# V_18.net
KiCad netlist of a schematic drawn in Altium Designer
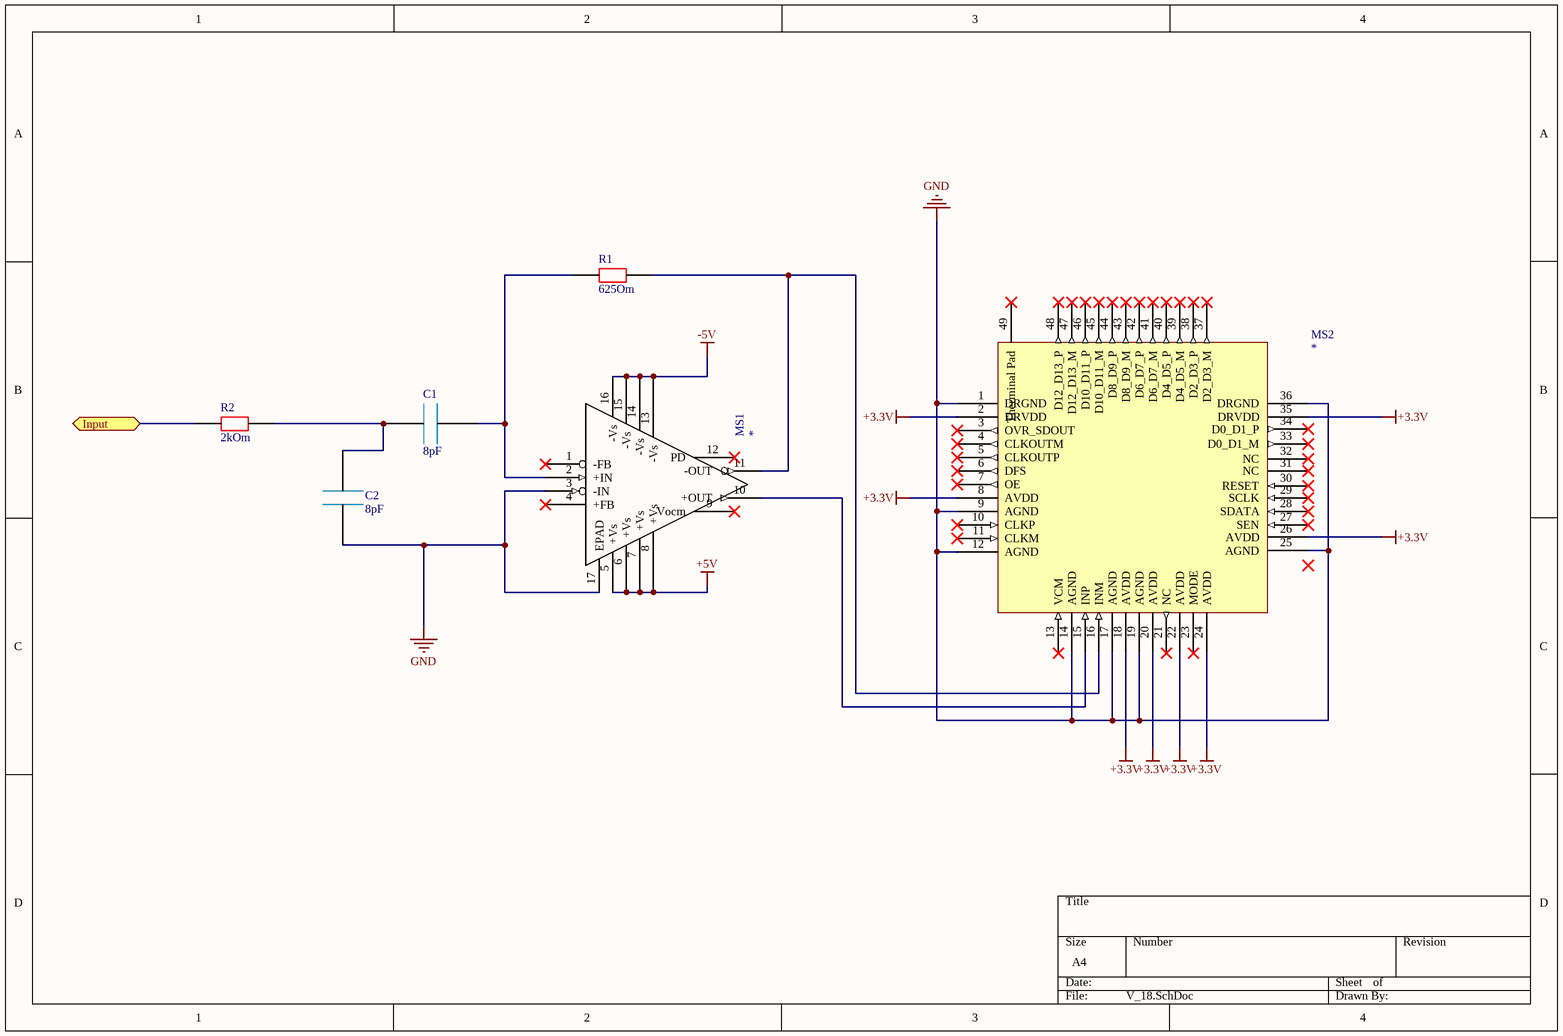
[diagram p0: V_18.SchDoc]

(export (version "E")
  (design (tool "Eeschema 10.0.6"))
  (components
    (comp (ref "C1") (value "8pF") (footprint "V_18:Ñ1") (libsource (lib "V_18") (part "Ñ1")))
    (comp (ref "C2") (value "8pF") (footprint "V_18:Ñ1") (libsource (lib "V_18") (part "Ñ1")))
    (comp (ref "MS1") (value "*") (footprint "V_18:ADA4932") (libsource (lib "V_18") (part "ADA4932")))
    (comp (ref "MS2") (value "*") (footprint "V_18:ADS61B49") (libsource (lib "V_18") (part "ADS61B49")))
    (comp (ref "R1") (value "625Om") (footprint "V_18:Res0805") (libsource (lib "V_18") (part "Res")))
    (comp (ref "R2") (value "2kOm") (footprint "V_18:Res0805") (libsource (lib "V_18") (part "Res")))
  )
  (nets
    (net (code "1") (name "+3.3V") (class "Default")
      (node (ref "MS2") (pin "18") (pinfunction "AVDD_18") (pintype "power_in"))
      (node (ref "MS2") (pin "2") (pinfunction "DRVDD_2") (pintype "power_in"))
      (node (ref "MS2") (pin "20") (pinfunction "AVDD_20") (pintype "power_in"))
      (node (ref "MS2") (pin "22") (pinfunction "AVDD_22") (pintype "power_in"))
      (node (ref "MS2") (pin "24") (pinfunction "AVDD_24") (pintype "power_in"))
      (node (ref "MS2") (pin "26") (pinfunction "AVDD_26") (pintype "power_in"))
      (node (ref "MS2") (pin "35") (pinfunction "DRVDD_35") (pintype "power_in"))
      (node (ref "MS2") (pin "8") (pinfunction "AVDD_8") (pintype "power_in"))
    )
    (net (code "2") (name "+5V") (class "Default")
      (node (ref "MS1") (pin "5") (pinfunction "+Vs_5") (pintype "power_in"))
      (node (ref "MS1") (pin "6") (pinfunction "+Vs_6") (pintype "power_in"))
      (node (ref "MS1") (pin "7") (pinfunction "+Vs_7") (pintype "power_in"))
      (node (ref "MS1") (pin "8") (pinfunction "+Vs_8") (pintype "power_in"))
    )
    (net (code "3") (name "-5V") (class "Default")
      (node (ref "MS1") (pin "13") (pinfunction "-Vs_13") (pintype "power_in"))
      (node (ref "MS1") (pin "14") (pinfunction "-Vs_14") (pintype "power_in"))
      (node (ref "MS1") (pin "15") (pinfunction "-Vs_15") (pintype "power_in"))
      (node (ref "MS1") (pin "16") (pinfunction "-Vs_16") (pintype "power_in"))
    )
    (net (code "4") (name "/Input") (class "Default")
      (node (ref "R2") (pin "1") (pinfunction "1_1") (pintype "passive"))
    )
    (net (code "5") (name "GND") (class "Default")
      (node (ref "C2") (pin "54") (pinfunction "54_54") (pintype "passive"))
      (node (ref "MS1") (pin "17") (pinfunction "EPAD_17") (pintype "power_in"))
      (node (ref "MS1") (pin "3") (pinfunction "-IN_3") (pintype "input"))
      (node (ref "MS2") (pin "1") (pinfunction "DRGND_1") (pintype "power_in"))
      (node (ref "MS2") (pin "12") (pinfunction "AGND_12") (pintype "power_in"))
      (node (ref "MS2") (pin "14") (pinfunction "AGND_14") (pintype "power_in"))
      (node (ref "MS2") (pin "17") (pinfunction "AGND_17") (pintype "power_in"))
      (node (ref "MS2") (pin "19") (pinfunction "AGND_19") (pintype "power_in"))
      (node (ref "MS2") (pin "25") (pinfunction "AGND_25") (pintype "power_in"))
      (node (ref "MS2") (pin "36") (pinfunction "DRGND_36") (pintype "power_in"))
      (node (ref "MS2") (pin "9") (pinfunction "AGND_9") (pintype "power_in"))
    )
    (net (code "6") (name "Net-(C1-Pad53)") (class "Default")
      (node (ref "C1") (pin "53") (pinfunction "53_53") (pintype "passive"))
      (node (ref "C2") (pin "53") (pinfunction "53_53") (pintype "passive"))
      (node (ref "R2") (pin "2") (pinfunction "2_2") (pintype "passive"))
    )
    (net (code "7") (name "Net-(MS1-+IN)") (class "Default")
      (node (ref "C1") (pin "54") (pinfunction "54_54") (pintype "passive"))
      (node (ref "MS1") (pin "2") (pinfunction "+IN_2") (pintype "input"))
      (node (ref "R1") (pin "1") (pinfunction "1_1") (pintype "passive"))
    )
    (net (code "8") (name "Net-(MS1-+OUT)") (class "Default")
      (node (ref "MS1") (pin "10") (pinfunction "+OUT_10") (pintype "output"))
      (node (ref "MS2") (pin "15") (pinfunction "INP_15") (pintype "input"))
    )
    (net (code "9") (name "Net-(MS1--OUT)") (class "Default")
      (node (ref "MS1") (pin "11") (pinfunction "-OUT_11") (pintype "output"))
      (node (ref "MS2") (pin "16") (pinfunction "INM_16") (pintype "input"))
      (node (ref "R1") (pin "2") (pinfunction "2_2") (pintype "passive"))
    )
    (net (code "10") (name "unconnected-(MS1-+FB-Pad4)") (class "Default")
      (node (ref "MS1") (pin "4") (pinfunction "+FB_4") (pintype "passive+no_connect"))
    )
    (net (code "11") (name "unconnected-(MS1--FB-Pad1)") (class "Default")
      (node (ref "MS1") (pin "1") (pinfunction "-FB_1") (pintype "passive+no_connect"))
    )
    (net (code "12") (name "unconnected-(MS1-PD-Pad12)") (class "Default")
      (node (ref "MS1") (pin "12") (pinfunction "PD_12") (pintype "passive+no_connect"))
    )
    (net (code "13") (name "unconnected-(MS1-Vocm-Pad9)") (class "Default")
      (node (ref "MS1") (pin "9") (pinfunction "Vocm_9") (pintype "power_in+no_connect"))
    )
    (net (code "14") (name "unconnected-(MS2-CLKM-Pad11)") (class "Default")
      (node (ref "MS2") (pin "11") (pinfunction "CLKM_11") (pintype "input+no_connect"))
    )
    (net (code "15") (name "unconnected-(MS2-CLKOUTM-Pad4)") (class "Default")
      (node (ref "MS2") (pin "4") (pinfunction "CLKOUTM_4") (pintype "output+no_connect"))
    )
    (net (code "16") (name "unconnected-(MS2-CLKOUTP-Pad5)") (class "Default")
      (node (ref "MS2") (pin "5") (pinfunction "CLKOUTP_5") (pintype "output+no_connect"))
    )
    (net (code "17") (name "unconnected-(MS2-CLKP-Pad10)") (class "Default")
      (node (ref "MS2") (pin "10") (pinfunction "CLKP_10") (pintype "input+no_connect"))
    )
    (net (code "18") (name "unconnected-(MS2-D0_D1_M-Pad33)") (class "Default")
      (node (ref "MS2") (pin "33") (pinfunction "D0_D1_M_33") (pintype "output+no_connect"))
    )
    (net (code "19") (name "unconnected-(MS2-D0_D1_P-Pad34)") (class "Default")
      (node (ref "MS2") (pin "34") (pinfunction "D0_D1_P_34") (pintype "output+no_connect"))
    )
    (net (code "20") (name "unconnected-(MS2-D2_D3_M-Pad37)") (class "Default")
      (node (ref "MS2") (pin "37") (pinfunction "D2_D3_M_37") (pintype "output+no_connect"))
    )
    (net (code "21") (name "unconnected-(MS2-D2_D3_P-Pad38)") (class "Default")
      (node (ref "MS2") (pin "38") (pinfunction "D2_D3_P_38") (pintype "output+no_connect"))
    )
    (net (code "22") (name "unconnected-(MS2-D4_D5_M-Pad39)") (class "Default")
      (node (ref "MS2") (pin "39") (pinfunction "D4_D5_M_39") (pintype "output+no_connect"))
    )
    (net (code "23") (name "unconnected-(MS2-D4_D5_P-Pad40)") (class "Default")
      (node (ref "MS2") (pin "40") (pinfunction "D4_D5_P_40") (pintype "output+no_connect"))
    )
    (net (code "24") (name "unconnected-(MS2-D6_D7_M-Pad41)") (class "Default")
      (node (ref "MS2") (pin "41") (pinfunction "D6_D7_M_41") (pintype "output+no_connect"))
    )
    (net (code "25") (name "unconnected-(MS2-D6_D7_P-Pad42)") (class "Default")
      (node (ref "MS2") (pin "42") (pinfunction "D6_D7_P_42") (pintype "output+no_connect"))
    )
    (net (code "26") (name "unconnected-(MS2-D8_D9_M-Pad43)") (class "Default")
      (node (ref "MS2") (pin "43") (pinfunction "D8_D9_M_43") (pintype "output+no_connect"))
    )
    (net (code "27") (name "unconnected-(MS2-D8_D9_P-Pad44)") (class "Default")
      (node (ref "MS2") (pin "44") (pinfunction "D8_D9_P_44") (pintype "output+no_connect"))
    )
    (net (code "28") (name "unconnected-(MS2-D10_D11_M-Pad45)") (class "Default")
      (node (ref "MS2") (pin "45") (pinfunction "D10_D11_M_45") (pintype "output+no_connect"))
    )
    (net (code "29") (name "unconnected-(MS2-D10_D11_P-Pad46)") (class "Default")
      (node (ref "MS2") (pin "46") (pinfunction "D10_D11_P_46") (pintype "output+no_connect"))
    )
    (net (code "30") (name "unconnected-(MS2-D12_D13_M-Pad47)") (class "Default")
      (node (ref "MS2") (pin "47") (pinfunction "D12_D13_M_47") (pintype "output+no_connect"))
    )
    (net (code "31") (name "unconnected-(MS2-D12_D13_P-Pad48)") (class "Default")
      (node (ref "MS2") (pin "48") (pinfunction "D12_D13_P_48") (pintype "output+no_connect"))
    )
    (net (code "32") (name "unconnected-(MS2-DFS-Pad6)") (class "Default")
      (node (ref "MS2") (pin "6") (pinfunction "DFS_6") (pintype "output+no_connect"))
    )
    (net (code "33") (name "unconnected-(MS2-MODE-Pad23)") (class "Default")
      (node (ref "MS2") (pin "23") (pinfunction "MODE_23") (pintype "passive+no_connect"))
    )
    (net (code "34") (name "unconnected-(MS2-NC-Pad21)") (class "Default")
      (node (ref "MS2") (pin "21") (pinfunction "NC_21") (pintype "output+no_connect"))
    )
    (net (code "35") (name "unconnected-(MS2-NC-Pad31)") (class "Default")
      (node (ref "MS2") (pin "31") (pinfunction "NC_31") (pintype "passive+no_connect"))
    )
    (net (code "36") (name "unconnected-(MS2-NC-Pad32)") (class "Default")
      (node (ref "MS2") (pin "32") (pinfunction "NC_32") (pintype "passive+no_connect"))
    )
    (net (code "37") (name "unconnected-(MS2-OE-Pad7)") (class "Default")
      (node (ref "MS2") (pin "7") (pinfunction "OE_7") (pintype "output+no_connect"))
    )
    (net (code "38") (name "unconnected-(MS2-OVR_SDOUT-Pad3)") (class "Default")
      (node (ref "MS2") (pin "3") (pinfunction "OVR_SDOUT_3") (pintype "output+no_connect"))
    )
    (net (code "39") (name "unconnected-(MS2-RESET-Pad30)") (class "Default")
      (node (ref "MS2") (pin "30") (pinfunction "RESET_30") (pintype "input+no_connect"))
    )
    (net (code "40") (name "unconnected-(MS2-SCLK-Pad29)") (class "Default")
      (node (ref "MS2") (pin "29") (pinfunction "SCLK_29") (pintype "input+no_connect"))
    )
    (net (code "41") (name "unconnected-(MS2-SDATA-Pad28)") (class "Default")
      (node (ref "MS2") (pin "28") (pinfunction "SDATA_28") (pintype "input+no_connect"))
    )
    (net (code "42") (name "unconnected-(MS2-SEN-Pad27)") (class "Default")
      (node (ref "MS2") (pin "27") (pinfunction "SEN_27") (pintype "input+no_connect"))
    )
    (net (code "43") (name "unconnected-(MS2-Therminal_Pad-Pad49)") (class "Default")
      (node (ref "MS2") (pin "49") (pinfunction "Therminal_Pad_49") (pintype "power_in+no_connect"))
    )
    (net (code "44") (name "unconnected-(MS2-VCM-Pad13)") (class "Default")
      (node (ref "MS2") (pin "13") (pinfunction "VCM_13") (pintype "input+no_connect"))
    )
  )
)
